# Cartridge_Relocator_rev1.net
KiCad netlist of a schematic drawn in EAGLE
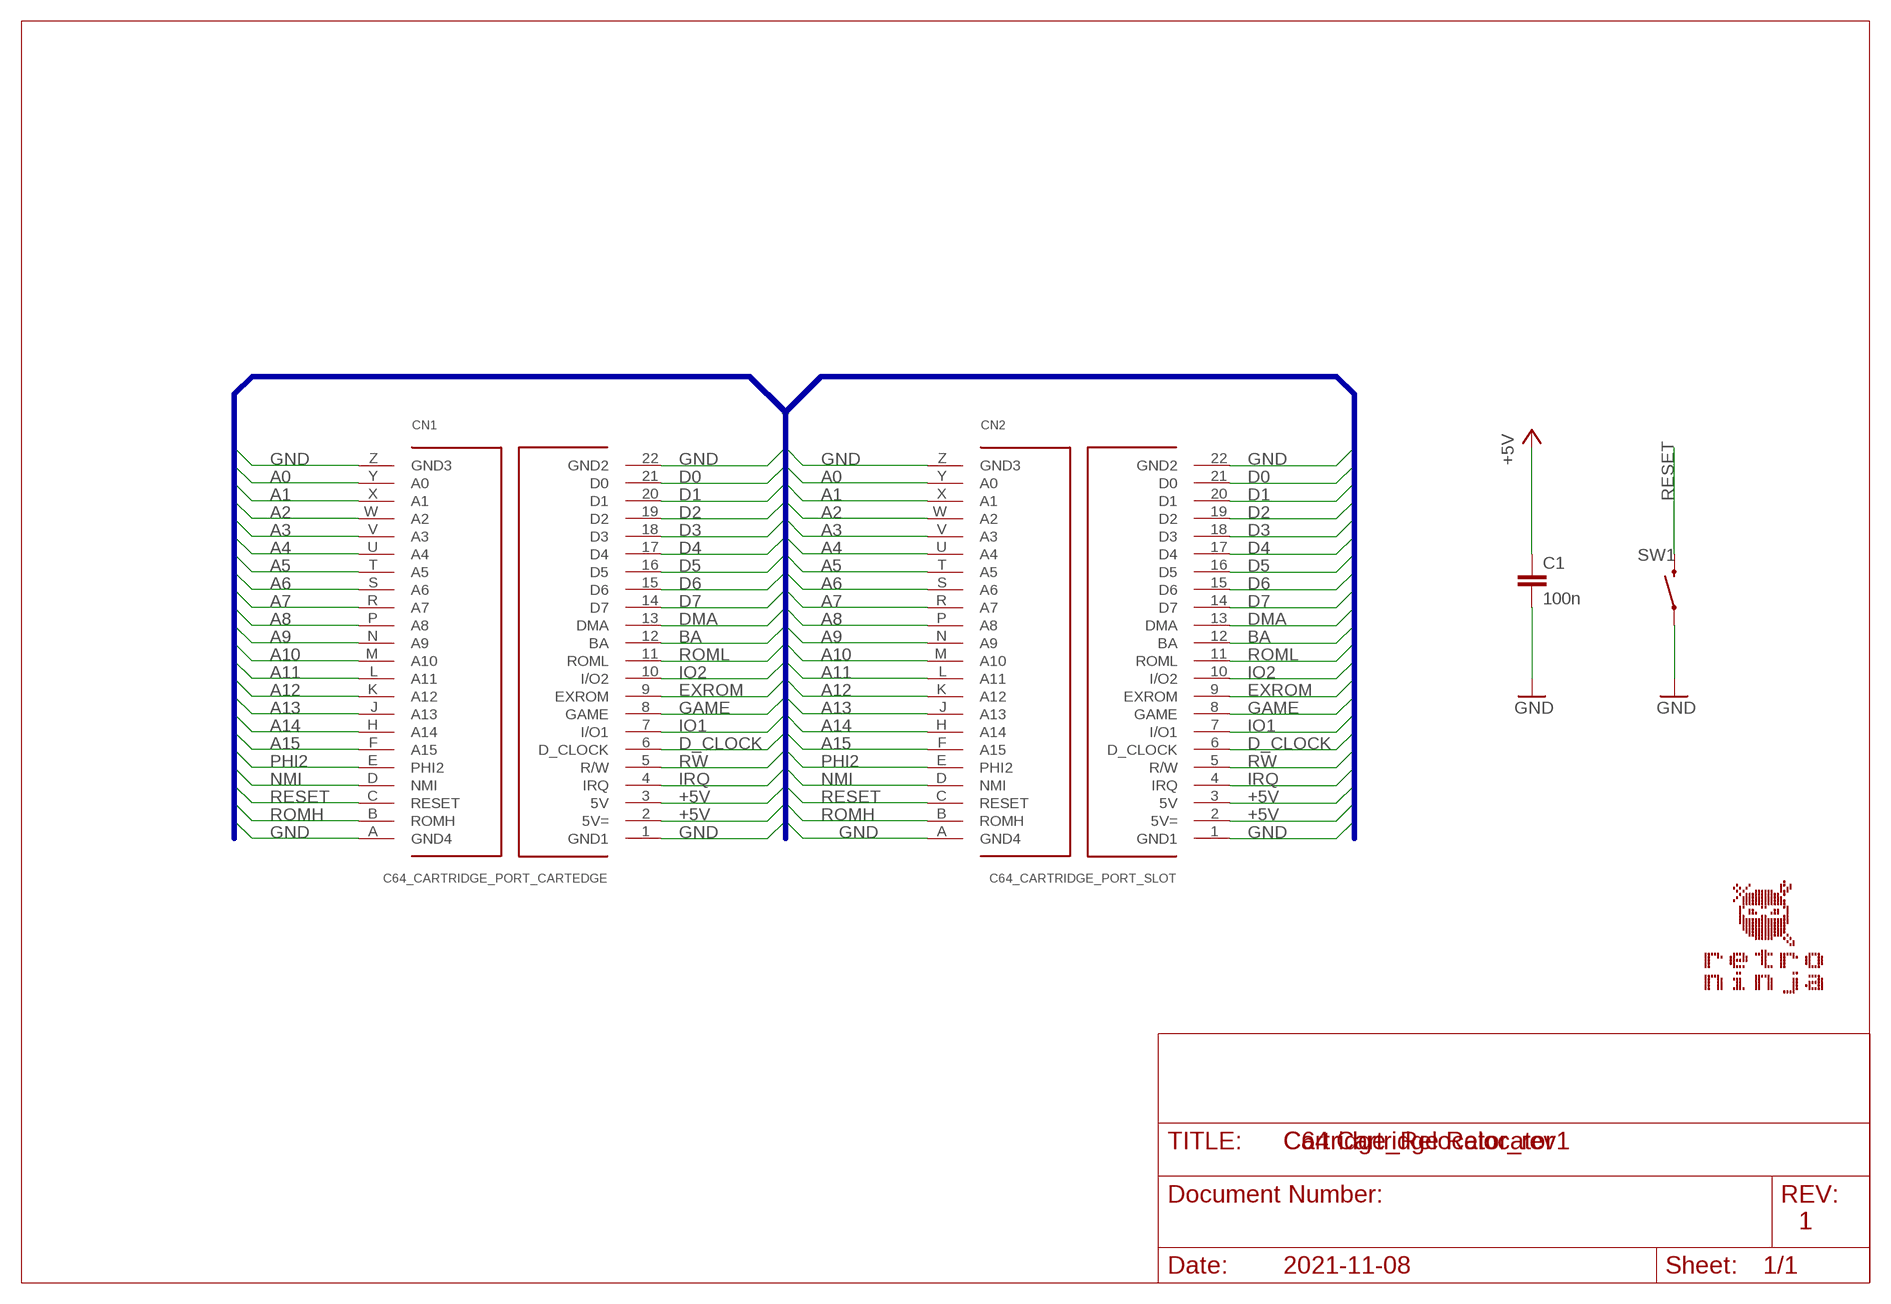
[diagram p0: schematic, sheet 1]

(export (version "E")
  (design (tool "Eeschema 10.0.6"))
  (components
    (comp (ref "C1")
      (value "100n")
      (footprint "eagle-import:CAP_5MM_2.5X5.0_ROUND")
      (libsource (lib "eagle-import") (part "CAPACITOR-5"))
    )
    (comp (ref "CN1")
      (value "C64_CARTRIDGE_PORT_CARTEDGE")
      (footprint "eagle-import:C64_CARTRIDGE_BOARDEDGE")
      (libsource (lib "eagle-import") (part "C64_CARTRIDGE_PORT_CARTEDGE"))
    )
    (comp (ref "CN2")
      (value "C64_CARTRIDGE_PORT_SLOT")
      (footprint "eagle-import:C64_CARTRIDGE_SLOT")
      (libsource (lib "eagle-import") (part "C64_CARTRIDGE_PORT_SLOT"))
    )
    (comp (ref "SW1")
      (value "SWITCH_MOMENTARY")
      (footprint "eagle-import:SWITCH_MOM_6.0MMX5.0MM")
      (libsource (lib "eagle-import") (part "SWITCH_MOMENTARY"))
    )
  )
  (nets
    (net (code "1") (name "+5V") (class "Default")
      (node (ref "C1") (pin "1") (pinfunction "1_1") (pintype "passive"))
      (node (ref "CN1") (pin "2") (pinfunction "5V=_2") (pintype "bidirectional"))
      (node (ref "CN1") (pin "3") (pinfunction "5V_3") (pintype "bidirectional"))
      (node (ref "CN2") (pin "2") (pinfunction "5V=_2") (pintype "bidirectional"))
      (node (ref "CN2") (pin "3") (pinfunction "5V_3") (pintype "bidirectional"))
    )
    (net (code "2") (name "/A0") (class "Default")
      (node (ref "CN1") (pin "Y") (pinfunction "A0_Y") (pintype "bidirectional"))
      (node (ref "CN2") (pin "Y") (pinfunction "A0_Y") (pintype "bidirectional"))
    )
    (net (code "3") (name "/A1") (class "Default")
      (node (ref "CN1") (pin "X") (pinfunction "A1_X") (pintype "bidirectional"))
      (node (ref "CN2") (pin "X") (pinfunction "A1_X") (pintype "bidirectional"))
    )
    (net (code "4") (name "/A2") (class "Default")
      (node (ref "CN1") (pin "W") (pinfunction "A2_W") (pintype "bidirectional"))
      (node (ref "CN2") (pin "W") (pinfunction "A2_W") (pintype "bidirectional"))
    )
    (net (code "5") (name "/A3") (class "Default")
      (node (ref "CN1") (pin "V") (pinfunction "A3_V") (pintype "bidirectional"))
      (node (ref "CN2") (pin "V") (pinfunction "A3_V") (pintype "bidirectional"))
    )
    (net (code "6") (name "/A4") (class "Default")
      (node (ref "CN1") (pin "U") (pinfunction "A4_U") (pintype "bidirectional"))
      (node (ref "CN2") (pin "U") (pinfunction "A4_U") (pintype "bidirectional"))
    )
    (net (code "7") (name "/A5") (class "Default")
      (node (ref "CN1") (pin "T") (pinfunction "A5_T") (pintype "bidirectional"))
      (node (ref "CN2") (pin "T") (pinfunction "A5_T") (pintype "bidirectional"))
    )
    (net (code "8") (name "/A6") (class "Default")
      (node (ref "CN1") (pin "S") (pinfunction "A6_S") (pintype "bidirectional"))
      (node (ref "CN2") (pin "S") (pinfunction "A6_S") (pintype "bidirectional"))
    )
    (net (code "9") (name "/A7") (class "Default")
      (node (ref "CN1") (pin "R") (pinfunction "A7_R") (pintype "bidirectional"))
      (node (ref "CN2") (pin "R") (pinfunction "A7_R") (pintype "bidirectional"))
    )
    (net (code "10") (name "/A8") (class "Default")
      (node (ref "CN1") (pin "P") (pinfunction "A8_P") (pintype "bidirectional"))
      (node (ref "CN2") (pin "P") (pinfunction "A8_P") (pintype "bidirectional"))
    )
    (net (code "11") (name "/A9") (class "Default")
      (node (ref "CN1") (pin "N") (pinfunction "A9_N") (pintype "bidirectional"))
      (node (ref "CN2") (pin "N") (pinfunction "A9_N") (pintype "bidirectional"))
    )
    (net (code "12") (name "/A10") (class "Default")
      (node (ref "CN1") (pin "M") (pinfunction "A10_M") (pintype "bidirectional"))
      (node (ref "CN2") (pin "M") (pinfunction "A10_M") (pintype "bidirectional"))
    )
    (net (code "13") (name "/A11") (class "Default")
      (node (ref "CN1") (pin "L") (pinfunction "A11_L") (pintype "bidirectional"))
      (node (ref "CN2") (pin "L") (pinfunction "A11_L") (pintype "bidirectional"))
    )
    (net (code "14") (name "/A12") (class "Default")
      (node (ref "CN1") (pin "K") (pinfunction "A12_K") (pintype "bidirectional"))
      (node (ref "CN2") (pin "K") (pinfunction "A12_K") (pintype "bidirectional"))
    )
    (net (code "15") (name "/A13") (class "Default")
      (node (ref "CN1") (pin "J") (pinfunction "A13_J") (pintype "bidirectional"))
      (node (ref "CN2") (pin "J") (pinfunction "A13_J") (pintype "bidirectional"))
    )
    (net (code "16") (name "/A14") (class "Default")
      (node (ref "CN1") (pin "H") (pinfunction "A14_H") (pintype "bidirectional"))
      (node (ref "CN2") (pin "H") (pinfunction "A14_H") (pintype "bidirectional"))
    )
    (net (code "17") (name "/A15") (class "Default")
      (node (ref "CN1") (pin "F") (pinfunction "A15_F") (pintype "bidirectional"))
      (node (ref "CN2") (pin "F") (pinfunction "A15_F") (pintype "bidirectional"))
    )
    (net (code "18") (name "/BA") (class "Default")
      (node (ref "CN1") (pin "12") (pinfunction "BA_12") (pintype "bidirectional"))
      (node (ref "CN2") (pin "12") (pinfunction "BA_12") (pintype "bidirectional"))
    )
    (net (code "19") (name "/D0") (class "Default")
      (node (ref "CN1") (pin "21") (pinfunction "D0_21") (pintype "bidirectional"))
      (node (ref "CN2") (pin "21") (pinfunction "D0_21") (pintype "bidirectional"))
    )
    (net (code "20") (name "/D1") (class "Default")
      (node (ref "CN1") (pin "20") (pinfunction "D1_20") (pintype "bidirectional"))
      (node (ref "CN2") (pin "20") (pinfunction "D1_20") (pintype "bidirectional"))
    )
    (net (code "21") (name "/D2") (class "Default")
      (node (ref "CN1") (pin "19") (pinfunction "D2_19") (pintype "bidirectional"))
      (node (ref "CN2") (pin "19") (pinfunction "D2_19") (pintype "bidirectional"))
    )
    (net (code "22") (name "/D3") (class "Default")
      (node (ref "CN1") (pin "18") (pinfunction "D3_18") (pintype "bidirectional"))
      (node (ref "CN2") (pin "18") (pinfunction "D3_18") (pintype "bidirectional"))
    )
    (net (code "23") (name "/D4") (class "Default")
      (node (ref "CN1") (pin "17") (pinfunction "D4_17") (pintype "bidirectional"))
      (node (ref "CN2") (pin "17") (pinfunction "D4_17") (pintype "bidirectional"))
    )
    (net (code "24") (name "/D5") (class "Default")
      (node (ref "CN1") (pin "16") (pinfunction "D5_16") (pintype "bidirectional"))
      (node (ref "CN2") (pin "16") (pinfunction "D5_16") (pintype "bidirectional"))
    )
    (net (code "25") (name "/D6") (class "Default")
      (node (ref "CN1") (pin "15") (pinfunction "D6_15") (pintype "bidirectional"))
      (node (ref "CN2") (pin "15") (pinfunction "D6_15") (pintype "bidirectional"))
    )
    (net (code "26") (name "/D7") (class "Default")
      (node (ref "CN1") (pin "14") (pinfunction "D7_14") (pintype "bidirectional"))
      (node (ref "CN2") (pin "14") (pinfunction "D7_14") (pintype "bidirectional"))
    )
    (net (code "27") (name "/DMA") (class "Default")
      (node (ref "CN1") (pin "13") (pinfunction "DMA_13") (pintype "bidirectional"))
      (node (ref "CN2") (pin "13") (pinfunction "DMA_13") (pintype "bidirectional"))
    )
    (net (code "28") (name "/D_CLOCK") (class "Default")
      (node (ref "CN1") (pin "6") (pinfunction "D_CLOCK_6") (pintype "bidirectional"))
      (node (ref "CN2") (pin "6") (pinfunction "D_CLOCK_6") (pintype "bidirectional"))
    )
    (net (code "29") (name "/EXROM") (class "Default")
      (node (ref "CN1") (pin "9") (pinfunction "EXROM_9") (pintype "bidirectional"))
      (node (ref "CN2") (pin "9") (pinfunction "EXROM_9") (pintype "bidirectional"))
    )
    (net (code "30") (name "/GAME") (class "Default")
      (node (ref "CN1") (pin "8") (pinfunction "GAME_8") (pintype "bidirectional"))
      (node (ref "CN2") (pin "8") (pinfunction "GAME_8") (pintype "bidirectional"))
    )
    (net (code "31") (name "/IO1") (class "Default")
      (node (ref "CN1") (pin "7") (pinfunction "I/O1_7") (pintype "bidirectional"))
      (node (ref "CN2") (pin "7") (pinfunction "I/O1_7") (pintype "bidirectional"))
    )
    (net (code "32") (name "/IO2") (class "Default")
      (node (ref "CN1") (pin "10") (pinfunction "I/O2_10") (pintype "bidirectional"))
      (node (ref "CN2") (pin "10") (pinfunction "I/O2_10") (pintype "bidirectional"))
    )
    (net (code "33") (name "/IRQ") (class "Default")
      (node (ref "CN1") (pin "4") (pinfunction "IRQ_4") (pintype "bidirectional"))
      (node (ref "CN2") (pin "4") (pinfunction "IRQ_4") (pintype "bidirectional"))
    )
    (net (code "34") (name "/NMI") (class "Default")
      (node (ref "CN1") (pin "D") (pinfunction "NMI_D") (pintype "bidirectional"))
      (node (ref "CN2") (pin "D") (pinfunction "NMI_D") (pintype "bidirectional"))
    )
    (net (code "35") (name "/PHI2") (class "Default")
      (node (ref "CN1") (pin "E") (pinfunction "PHI2_E") (pintype "bidirectional"))
      (node (ref "CN2") (pin "E") (pinfunction "PHI2_E") (pintype "bidirectional"))
    )
    (net (code "36") (name "/RESET") (class "Default")
      (node (ref "CN1") (pin "C") (pinfunction "RESET_C") (pintype "bidirectional"))
      (node (ref "CN2") (pin "C") (pinfunction "RESET_C") (pintype "bidirectional"))
      (node (ref "SW1") (pin "3") (pinfunction "2_3") (pintype "passive"))
      (node (ref "SW1") (pin "4") (pinfunction "2_4") (pintype "passive"))
    )
    (net (code "37") (name "/ROMH") (class "Default")
      (node (ref "CN1") (pin "B") (pinfunction "ROMH_B") (pintype "bidirectional"))
      (node (ref "CN2") (pin "B") (pinfunction "ROMH_B") (pintype "bidirectional"))
    )
    (net (code "38") (name "/ROML") (class "Default")
      (node (ref "CN1") (pin "11") (pinfunction "ROML_11") (pintype "bidirectional"))
      (node (ref "CN2") (pin "11") (pinfunction "ROML_11") (pintype "bidirectional"))
    )
    (net (code "39") (name "/RW") (class "Default")
      (node (ref "CN1") (pin "5") (pinfunction "R/W_5") (pintype "bidirectional"))
      (node (ref "CN2") (pin "5") (pinfunction "R/W_5") (pintype "bidirectional"))
    )
    (net (code "40") (name "GND") (class "Default")
      (node (ref "C1") (pin "2") (pinfunction "2_2") (pintype "passive"))
      (node (ref "CN1") (pin "1") (pinfunction "GND1_1") (pintype "bidirectional"))
      (node (ref "CN1") (pin "22") (pinfunction "GND2_22") (pintype "bidirectional"))
      (node (ref "CN1") (pin "A") (pinfunction "GND4_A") (pintype "bidirectional"))
      (node (ref "CN1") (pin "Z") (pinfunction "GND3_Z") (pintype "bidirectional"))
      (node (ref "CN2") (pin "1") (pinfunction "GND1_1") (pintype "bidirectional"))
      (node (ref "CN2") (pin "22") (pinfunction "GND2_22") (pintype "bidirectional"))
      (node (ref "CN2") (pin "A") (pinfunction "GND4_A") (pintype "bidirectional"))
      (node (ref "CN2") (pin "Z") (pinfunction "GND3_Z") (pintype "bidirectional"))
      (node (ref "SW1") (pin "1") (pinfunction "1_1") (pintype "passive"))
      (node (ref "SW1") (pin "2") (pinfunction "1_2") (pintype "passive"))
    )
  )
)
